# FT232RL_Programmer.net
KiCad netlist of a schematic drawn in Altium Designer
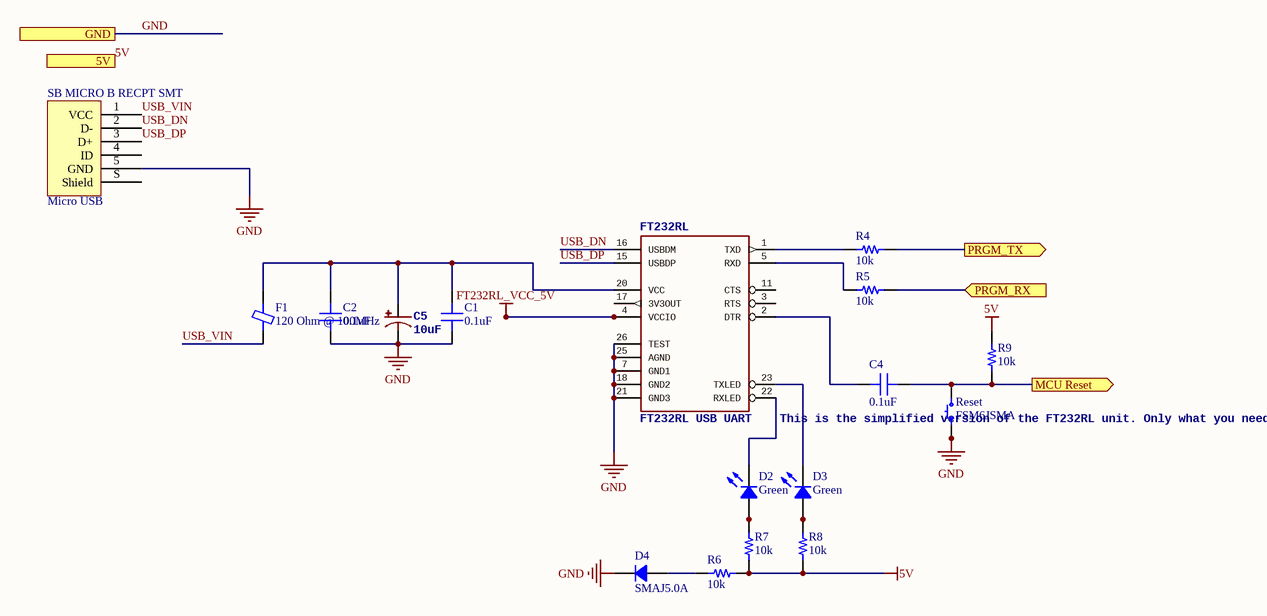
[diagram p0: FT232RL_Programmer.SchDoc]

(export (version "E")
  (design (tool "Eeschema 10.0.6"))
  (components
    (comp (ref "C1")
      (value "0.1uF")
      (footprint "CAP 0402/1005")
      (description "CAP CER 0.1UF 16V X7R 0402")
      (fields
        (field (name "PART NUMBER") "C1005X7R1C104K050BC")
        (field (name "MANUFACTURER") "TDK Corporation")
      )
      (libsource (lib "Celestial Library Database") (part "Capacitor"))
    )
    (comp (ref "C2")
      (value "0.1uF")
      (footprint "CAP 0402/1005")
      (description "CAP CER 0.1UF 16V X7R 0402")
      (fields
        (field (name "PART NUMBER") "C1005X7R1C104K050BC")
        (field (name "MANUFACTURER") "TDK Corporation")
      )
      (libsource (lib "Celestial Library Database") (part "Capacitor"))
    )
    (comp (ref "C4")
      (value "0.1uF")
      (footprint "CAP 0402/1005")
      (description "CAP CER 0.1UF 16V X7R 0402")
      (fields
        (field (name "PART NUMBER") "C1005X7R1C104K050BC")
        (field (name "MANUFACTURER") "TDK Corporation")
      )
      (libsource (lib "Celestial Library Database") (part "Capacitor"))
    )
    (comp (ref "C5")
      (value "10uF")
      (footprint "CPOL-RADIAL-5MM-10MM-KIT")
      (libsource (lib "SparkFun-Capacitors") (part "1000UF-RADIAL-5MM-35V-20%-KIT"))
    )
    (comp (ref "D2")
      (value "Green")
      (footprint "LED 0603/1608 GREEN")
      (description "LED GREEN CLEAR 0603 SMD")
      (fields (field (name "PART NUMBER") "LTST-C191KGKT") (field (name "MANUFACTURER") "Lite-On Inc."))
      (libsource (lib "Celestial Library Database") (part "LED"))
    )
    (comp (ref "D3")
      (value "Green")
      (footprint "LED 0603/1608 GREEN")
      (description "LED GREEN CLEAR 0603 SMD")
      (fields (field (name "PART NUMBER") "LTST-C191KGKT") (field (name "MANUFACTURER") "Lite-On Inc."))
      (libsource (lib "Celestial Library Database") (part "LED"))
    )
    (comp (ref "D4")
      (value "SMAJ5.0A")
      (footprint "DO214AC SMA")
      (description "TVS DIODE 5VWM 9.2VC SMA")
      (fields (field (name "MANUFACTURER") "Littelfuse Inc."))
      (libsource (lib "Celestial Library Database") (part "Diode"))
    )
    (comp (ref "F1")
      (value "120 Ohm @ 100MHz")
      (footprint "FER 0201/0603")
      (description "FERRITE BEAD 120 OHM 0201 1LN")
      (fields
        (field (name "PART NUMBER") "BLM03AG121SN1D")
        (field (name "MANUFACTURER") "Murata Electronics North America")
      )
      (libsource (lib "Celestial Library Database") (part "Ferrite Chip"))
    )
    (comp (ref "FT232RL")
      (value "FT232RL USB UART    This is the simplified version of the FT232RL unit. Only what you need, nothing you don't.   FT232RL 4th Generation USB UART (USB <-> Serial) Controller.   Datasheet SparkFun Products  Component (COM-00650)  SparkFun RedBot Mainboard (ROB-12097)  SparkFun FTDI Basic Breakout - 5V (DEV-09716)  SparkFun FTDI Basic Breakout - 3.3V (DEV-09873)  Bus Pirate - v3.6a (TOL-12942)  SparkFun USB to Serial Breakout - FT232RL (BOB-12731)  SparkFun PicoBoard (WIG-11888)  SparkFun RFID USB Reader (SEN-09963)  LilyPad FTDI Basic Breakout - 5V (DEV-10275)  SparkFun Stepoko (ROB-13899)")
      (footprint "SSOP28DB")
      (libsource (lib "SparkFun-IC-Comms") (part "FT232RL-BASICSSOP"))
    )
    (comp (ref "R4")
      (value "10k")
      (footprint "RES 0402/1005")
      (description "RES SMD 10K OHM 1% 1/10W 0402")
      (fields
        (field (name "PART NUMBER") "ERJ-2RKF1002X")
        (field (name "MANUFACTURER") "Panasonic Electronic Components")
      )
      (libsource (lib "Celestial Library Database") (part "Resistor"))
    )
    (comp (ref "R5")
      (value "10k")
      (footprint "RES 0402/1005")
      (description "RES SMD 10K OHM 1% 1/10W 0402")
      (fields
        (field (name "PART NUMBER") "ERJ-2RKF1002X")
        (field (name "MANUFACTURER") "Panasonic Electronic Components")
      )
      (libsource (lib "Celestial Library Database") (part "Resistor"))
    )
    (comp (ref "R6")
      (value "10k")
      (footprint "RES 0402/1005")
      (description "RES SMD 10K OHM 1% 1/10W 0402")
      (fields
        (field (name "PART NUMBER") "ERJ-2RKF1002X")
        (field (name "MANUFACTURER") "Panasonic Electronic Components")
      )
      (libsource (lib "Celestial Library Database") (part "Resistor"))
    )
    (comp (ref "R7")
      (value "10k")
      (footprint "RES 0402/1005")
      (description "RES SMD 10K OHM 1% 1/10W 0402")
      (fields
        (field (name "PART NUMBER") "ERJ-2RKF1002X")
        (field (name "MANUFACTURER") "Panasonic Electronic Components")
      )
      (libsource (lib "Celestial Library Database") (part "Resistor"))
    )
    (comp (ref "R8")
      (value "10k")
      (footprint "RES 0402/1005")
      (description "RES SMD 10K OHM 1% 1/10W 0402")
      (fields
        (field (name "PART NUMBER") "ERJ-2RKF1002X")
        (field (name "MANUFACTURER") "Panasonic Electronic Components")
      )
      (libsource (lib "Celestial Library Database") (part "Resistor"))
    )
    (comp (ref "R9")
      (value "10k")
      (footprint "RES 0402/1005")
      (description "RES SMD 10K OHM 1% 1/10W 0402")
      (fields
        (field (name "PART NUMBER") "ERJ-2RKF1002X")
        (field (name "MANUFACTURER") "Panasonic Electronic Components")
      )
      (libsource (lib "Celestial Library Database") (part "Resistor"))
    )
    (comp (ref "Reset")
      (value "FSM6JSMA")
      (footprint "TE FSM6JSMA")
      (description "SWITCH TACTILE SPST-NO 0.05A 24V")
      (fields (field (name "MANUFACTURER") "TE Connectivity Alcoswitch Switches"))
      (libsource (lib "Celestial Library Database") (part "SPST-NO 4 PIN"))
    )
    (comp (ref "SB MICRO B RECPT SMT")
      (value "Micro USB")
      (footprint "FCI USB 10118193-0001LF")
      (description "CONN USB MICRO B RECPT SMT R/A")
      (fields (field (name "PART NUMBER") "10118193-0001LF") (field (name "MANUFACTURER") "FCI"))
      (libsource (lib "Celestial Library Database") (part "USB 2.0 Type B Micro"))
    )
  )
  (nets
    (net (code "1") (name "/MCU Reset") (class "Default")
      (node (ref "C4") (pin "2") (pinfunction "2_2") (pintype "passive"))
      (node (ref "R9") (pin "1") (pinfunction "1_1") (pintype "passive"))
      (node (ref "Reset") (pin "3") (pinfunction "3_3") (pintype "passive"))
      (node (ref "Reset") (pin "4") (pinfunction "4_4") (pintype "passive"))
    )
    (net (code "2") (name "/PRGM_RX") (class "Default")
      (node (ref "R5") (pin "2") (pinfunction "2_2") (pintype "passive"))
    )
    (net (code "3") (name "/PRGM_TX") (class "Default")
      (node (ref "R4") (pin "2") (pinfunction "2_2") (pintype "passive"))
    )
    (net (code "4") (name "/USB_DN") (class "Default")
      (node (ref "FT232RL") (pin "16") (pinfunction "USBDM_16") (pintype "passive"))
      (node (ref "SB MICRO B RECPT SMT") (pin "2") (pinfunction "D-_2") (pintype "passive"))
    )
    (net (code "5") (name "/USB_DP") (class "Default")
      (node (ref "FT232RL") (pin "15") (pinfunction "USBDP_15") (pintype "passive"))
      (node (ref "SB MICRO B RECPT SMT") (pin "3") (pinfunction "D+_3") (pintype "passive"))
    )
    (net (code "6") (name "/USB_VIN") (class "Default")
      (node (ref "F1") (pin "1") (pinfunction "1_1") (pintype "passive"))
      (node (ref "SB MICRO B RECPT SMT") (pin "1") (pinfunction "VCC_1") (pintype "passive"))
    )
    (net (code "7") (name "5V") (class "Default")
      (node (ref "R6") (pin "1") (pinfunction "1_1") (pintype "passive"))
      (node (ref "R7") (pin "1") (pinfunction "1_1") (pintype "passive"))
      (node (ref "R8") (pin "1") (pinfunction "1_1") (pintype "passive"))
      (node (ref "R9") (pin "2") (pinfunction "2_2") (pintype "passive"))
    )
    (net (code "8") (name "FT232RL_VCC_5V") (class "Default")
      (node (ref "FT232RL") (pin "4") (pinfunction "VCCIO_4") (pintype "power_in"))
    )
    (net (code "9") (name "GND") (class "Default")
      (node (ref "C1") (pin "1") (pinfunction "1_1") (pintype "passive"))
      (node (ref "C2") (pin "1") (pinfunction "1_1") (pintype "passive"))
      (node (ref "C5") (pin "-") (pinfunction "-_-") (pintype "passive"))
      (node (ref "D4") (pin "2") (pinfunction "2_2") (pintype "passive"))
      (node (ref "FT232RL") (pin "18") (pinfunction "GND2_18") (pintype "power_in"))
      (node (ref "FT232RL") (pin "21") (pinfunction "GND3_21") (pintype "power_in"))
      (node (ref "FT232RL") (pin "25") (pinfunction "AGND_25") (pintype "power_in"))
      (node (ref "FT232RL") (pin "26") (pinfunction "TEST_26") (pintype "passive"))
      (node (ref "FT232RL") (pin "7") (pinfunction "GND1_7") (pintype "power_in"))
      (node (ref "Reset") (pin "1") (pinfunction "1_1") (pintype "passive"))
      (node (ref "Reset") (pin "2") (pinfunction "2_2") (pintype "passive"))
      (node (ref "SB MICRO B RECPT SMT") (pin "5") (pinfunction "GND_5") (pintype "passive"))
    )
    (net (code "10") (name "Net-(D2-Pad1)") (class "Default")
      (node (ref "D2") (pin "1") (pinfunction "1_1") (pintype "passive"))
      (node (ref "R7") (pin "2") (pinfunction "2_2") (pintype "passive"))
    )
    (net (code "11") (name "Net-(D3-Pad1)") (class "Default")
      (node (ref "D3") (pin "1") (pinfunction "1_1") (pintype "passive"))
      (node (ref "R8") (pin "2") (pinfunction "2_2") (pintype "passive"))
    )
    (net (code "12") (name "Net-(D4-Pad1)") (class "Default")
      (node (ref "D4") (pin "1") (pinfunction "1_1") (pintype "passive"))
      (node (ref "R6") (pin "2") (pinfunction "2_2") (pintype "passive"))
    )
    (net (code "13") (name "Net-(FT232RL-DTR)") (class "Default")
      (node (ref "C4") (pin "1") (pinfunction "1_1") (pintype "passive"))
      (node (ref "FT232RL") (pin "2") (pinfunction "DTR_2") (pintype "passive"))
    )
    (net (code "14") (name "Net-(FT232RL-RXD)") (class "Default")
      (node (ref "FT232RL") (pin "5") (pinfunction "RXD_5") (pintype "passive"))
      (node (ref "R5") (pin "1") (pinfunction "1_1") (pintype "passive"))
    )
    (net (code "15") (name "Net-(FT232RL-RXLED)") (class "Default")
      (node (ref "D2") (pin "2") (pinfunction "2_2") (pintype "passive"))
      (node (ref "FT232RL") (pin "22") (pinfunction "RXLED_22") (pintype "passive"))
    )
    (net (code "16") (name "Net-(FT232RL-TXD)") (class "Default")
      (node (ref "FT232RL") (pin "1") (pinfunction "TXD_1") (pintype "output"))
      (node (ref "R4") (pin "1") (pinfunction "1_1") (pintype "passive"))
    )
    (net (code "17") (name "Net-(FT232RL-TXLED)") (class "Default")
      (node (ref "D3") (pin "2") (pinfunction "2_2") (pintype "passive"))
      (node (ref "FT232RL") (pin "23") (pinfunction "TXLED_23") (pintype "passive"))
    )
    (net (code "18") (name "Net-(FT232RL-VCC)") (class "Default")
      (node (ref "C1") (pin "2") (pinfunction "2_2") (pintype "passive"))
      (node (ref "C2") (pin "2") (pinfunction "2_2") (pintype "passive"))
      (node (ref "C5") (pin "+") (pinfunction "+_+") (pintype "passive"))
      (node (ref "F1") (pin "2") (pinfunction "2_2") (pintype "passive"))
      (node (ref "FT232RL") (pin "20") (pinfunction "VCC_20") (pintype "power_in"))
    )
    (net (code "19") (name "unconnected-(FT232RL-3V3OUT-Pad17)") (class "Default")
      (node (ref "FT232RL") (pin "17") (pinfunction "3V3OUT_17") (pintype "output"))
    )
    (net (code "20") (name "unconnected-(FT232RL-CTS-Pad11)") (class "Default")
      (node (ref "FT232RL") (pin "11") (pinfunction "CTS_11") (pintype "passive"))
    )
    (net (code "21") (name "unconnected-(FT232RL-RTS-Pad3)") (class "Default")
      (node (ref "FT232RL") (pin "3") (pinfunction "RTS_3") (pintype "passive"))
    )
    (net (code "22") (name "unconnected-(SB MICRO B RECPT SMT-ID-Pad4)") (class "Default")
      (node (ref "SB MICRO B RECPT SMT") (pin "4") (pinfunction "ID_4") (pintype "passive"))
    )
    (net (code "23") (name "unconnected-(SB MICRO B RECPT SMT-Shield-PadS)") (class "Default")
      (node (ref "SB MICRO B RECPT SMT") (pin "S") (pinfunction "Shield_S") (pintype "passive"))
    )
  )
)
